# JETSON_AGX_UPHY.net
KiCad netlist of a schematic drawn in Altium Designer
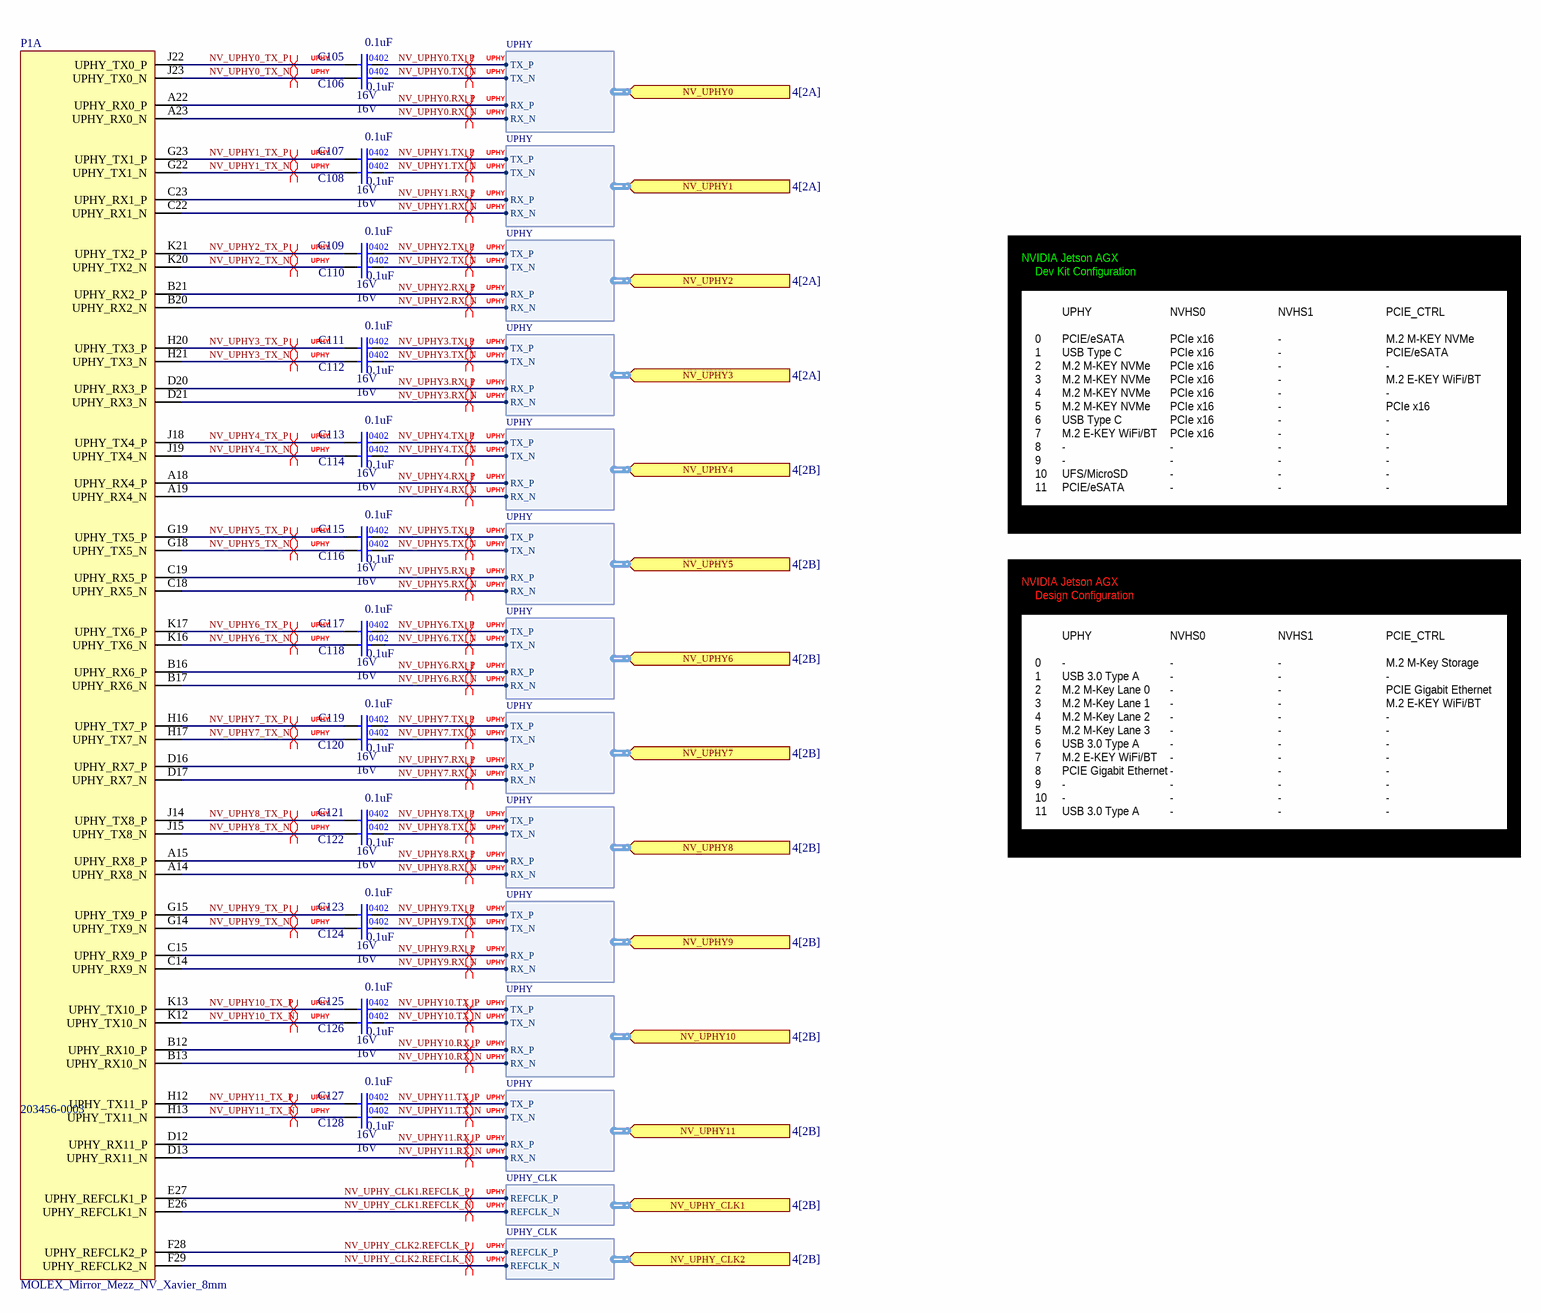
[diagram p0: JETSON AGX UPHY.SchDoc]

(export (version "E")
  (design (tool "Eeschema 10.0.6"))
  (components
    (comp (ref "C105")
      (value "CAP_0.1uF_16V_X7R_0402")
      (footprint "CAP0402")
      (description "CAP CER 0.1UF 16V X7R 0402")
      (fields (field (name "CAPACITANCE") "0.1uF") (field (name "VOLTAGE RATING") "16V"))
      (libsource (lib "UWRT_Schematic_Library_2020") (part "CAP_0.1uF_16V_X7R_0402"))
    )
    (comp (ref "C106")
      (value "CAP_0.1uF_16V_X7R_0402")
      (footprint "CAP0402")
      (description "CAP CER 0.1UF 16V X7R 0402")
      (fields (field (name "CAPACITANCE") "0.1uF") (field (name "VOLTAGE RATING") "16V"))
      (libsource (lib "UWRT_Schematic_Library_2020") (part "CAP_0.1uF_16V_X7R_0402"))
    )
    (comp (ref "C107")
      (value "CAP_0.1uF_16V_X7R_0402")
      (footprint "CAP0402")
      (description "CAP CER 0.1UF 16V X7R 0402")
      (fields (field (name "CAPACITANCE") "0.1uF") (field (name "VOLTAGE RATING") "16V"))
      (libsource (lib "UWRT_Schematic_Library_2020") (part "CAP_0.1uF_16V_X7R_0402"))
    )
    (comp (ref "C108")
      (value "CAP_0.1uF_16V_X7R_0402")
      (footprint "CAP0402")
      (description "CAP CER 0.1UF 16V X7R 0402")
      (fields (field (name "CAPACITANCE") "0.1uF") (field (name "VOLTAGE RATING") "16V"))
      (libsource (lib "UWRT_Schematic_Library_2020") (part "CAP_0.1uF_16V_X7R_0402"))
    )
    (comp (ref "C109")
      (value "CAP_0.1uF_16V_X7R_0402")
      (footprint "CAP0402")
      (description "CAP CER 0.1UF 16V X7R 0402")
      (fields (field (name "CAPACITANCE") "0.1uF") (field (name "VOLTAGE RATING") "16V"))
      (libsource (lib "UWRT_Schematic_Library_2020") (part "CAP_0.1uF_16V_X7R_0402"))
    )
    (comp (ref "C110")
      (value "CAP_0.1uF_16V_X7R_0402")
      (footprint "CAP0402")
      (description "CAP CER 0.1UF 16V X7R 0402")
      (fields (field (name "CAPACITANCE") "0.1uF") (field (name "VOLTAGE RATING") "16V"))
      (libsource (lib "UWRT_Schematic_Library_2020") (part "CAP_0.1uF_16V_X7R_0402"))
    )
    (comp (ref "C111")
      (value "CAP_0.1uF_16V_X7R_0402")
      (footprint "CAP0402")
      (description "CAP CER 0.1UF 16V X7R 0402")
      (fields (field (name "CAPACITANCE") "0.1uF") (field (name "VOLTAGE RATING") "16V"))
      (libsource (lib "UWRT_Schematic_Library_2020") (part "CAP_0.1uF_16V_X7R_0402"))
    )
    (comp (ref "C112")
      (value "CAP_0.1uF_16V_X7R_0402")
      (footprint "CAP0402")
      (description "CAP CER 0.1UF 16V X7R 0402")
      (fields (field (name "CAPACITANCE") "0.1uF") (field (name "VOLTAGE RATING") "16V"))
      (libsource (lib "UWRT_Schematic_Library_2020") (part "CAP_0.1uF_16V_X7R_0402"))
    )
    (comp (ref "C113")
      (value "CAP_0.1uF_16V_X7R_0402")
      (footprint "CAP0402")
      (description "CAP CER 0.1UF 16V X7R 0402")
      (fields (field (name "CAPACITANCE") "0.1uF") (field (name "VOLTAGE RATING") "16V"))
      (libsource (lib "UWRT_Schematic_Library_2020") (part "CAP_0.1uF_16V_X7R_0402"))
    )
    (comp (ref "C114")
      (value "CAP_0.1uF_16V_X7R_0402")
      (footprint "CAP0402")
      (description "CAP CER 0.1UF 16V X7R 0402")
      (fields (field (name "CAPACITANCE") "0.1uF") (field (name "VOLTAGE RATING") "16V"))
      (libsource (lib "UWRT_Schematic_Library_2020") (part "CAP_0.1uF_16V_X7R_0402"))
    )
    (comp (ref "C115")
      (value "CAP_0.1uF_16V_X7R_0402")
      (footprint "CAP0402")
      (description "CAP CER 0.1UF 16V X7R 0402")
      (fields (field (name "CAPACITANCE") "0.1uF") (field (name "VOLTAGE RATING") "16V"))
      (libsource (lib "UWRT_Schematic_Library_2020") (part "CAP_0.1uF_16V_X7R_0402"))
    )
    (comp (ref "C116")
      (value "CAP_0.1uF_16V_X7R_0402")
      (footprint "CAP0402")
      (description "CAP CER 0.1UF 16V X7R 0402")
      (fields (field (name "CAPACITANCE") "0.1uF") (field (name "VOLTAGE RATING") "16V"))
      (libsource (lib "UWRT_Schematic_Library_2020") (part "CAP_0.1uF_16V_X7R_0402"))
    )
    (comp (ref "C117")
      (value "CAP_0.1uF_16V_X7R_0402")
      (footprint "CAP0402")
      (description "CAP CER 0.1UF 16V X7R 0402")
      (fields (field (name "CAPACITANCE") "0.1uF") (field (name "VOLTAGE RATING") "16V"))
      (libsource (lib "UWRT_Schematic_Library_2020") (part "CAP_0.1uF_16V_X7R_0402"))
    )
    (comp (ref "C118")
      (value "CAP_0.1uF_16V_X7R_0402")
      (footprint "CAP0402")
      (description "CAP CER 0.1UF 16V X7R 0402")
      (fields (field (name "CAPACITANCE") "0.1uF") (field (name "VOLTAGE RATING") "16V"))
      (libsource (lib "UWRT_Schematic_Library_2020") (part "CAP_0.1uF_16V_X7R_0402"))
    )
    (comp (ref "C119")
      (value "CAP_0.1uF_16V_X7R_0402")
      (footprint "CAP0402")
      (description "CAP CER 0.1UF 16V X7R 0402")
      (fields (field (name "CAPACITANCE") "0.1uF") (field (name "VOLTAGE RATING") "16V"))
      (libsource (lib "UWRT_Schematic_Library_2020") (part "CAP_0.1uF_16V_X7R_0402"))
    )
    (comp (ref "C120")
      (value "CAP_0.1uF_16V_X7R_0402")
      (footprint "CAP0402")
      (description "CAP CER 0.1UF 16V X7R 0402")
      (fields (field (name "CAPACITANCE") "0.1uF") (field (name "VOLTAGE RATING") "16V"))
      (libsource (lib "UWRT_Schematic_Library_2020") (part "CAP_0.1uF_16V_X7R_0402"))
    )
    (comp (ref "C121")
      (value "CAP_0.1uF_16V_X7R_0402")
      (footprint "CAP0402")
      (description "CAP CER 0.1UF 16V X7R 0402")
      (fields (field (name "CAPACITANCE") "0.1uF") (field (name "VOLTAGE RATING") "16V"))
      (libsource (lib "UWRT_Schematic_Library_2020") (part "CAP_0.1uF_16V_X7R_0402"))
    )
    (comp (ref "C122")
      (value "CAP_0.1uF_16V_X7R_0402")
      (footprint "CAP0402")
      (description "CAP CER 0.1UF 16V X7R 0402")
      (fields (field (name "CAPACITANCE") "0.1uF") (field (name "VOLTAGE RATING") "16V"))
      (libsource (lib "UWRT_Schematic_Library_2020") (part "CAP_0.1uF_16V_X7R_0402"))
    )
    (comp (ref "C123")
      (value "CAP_0.1uF_16V_X7R_0402")
      (footprint "CAP0402")
      (description "CAP CER 0.1UF 16V X7R 0402")
      (fields (field (name "CAPACITANCE") "0.1uF") (field (name "VOLTAGE RATING") "16V"))
      (libsource (lib "UWRT_Schematic_Library_2020") (part "CAP_0.1uF_16V_X7R_0402"))
    )
    (comp (ref "C124")
      (value "CAP_0.1uF_16V_X7R_0402")
      (footprint "CAP0402")
      (description "CAP CER 0.1UF 16V X7R 0402")
      (fields (field (name "CAPACITANCE") "0.1uF") (field (name "VOLTAGE RATING") "16V"))
      (libsource (lib "UWRT_Schematic_Library_2020") (part "CAP_0.1uF_16V_X7R_0402"))
    )
    (comp (ref "C125")
      (value "CAP_0.1uF_16V_X7R_0402")
      (footprint "CAP0402")
      (description "CAP CER 0.1UF 16V X7R 0402")
      (fields (field (name "CAPACITANCE") "0.1uF") (field (name "VOLTAGE RATING") "16V"))
      (libsource (lib "UWRT_Schematic_Library_2020") (part "CAP_0.1uF_16V_X7R_0402"))
    )
    (comp (ref "C126")
      (value "CAP_0.1uF_16V_X7R_0402")
      (footprint "CAP0402")
      (description "CAP CER 0.1UF 16V X7R 0402")
      (fields (field (name "CAPACITANCE") "0.1uF") (field (name "VOLTAGE RATING") "16V"))
      (libsource (lib "UWRT_Schematic_Library_2020") (part "CAP_0.1uF_16V_X7R_0402"))
    )
    (comp (ref "C127")
      (value "CAP_0.1uF_16V_X7R_0402")
      (footprint "CAP0402")
      (description "CAP CER 0.1UF 16V X7R 0402")
      (fields (field (name "CAPACITANCE") "0.1uF") (field (name "VOLTAGE RATING") "16V"))
      (libsource (lib "UWRT_Schematic_Library_2020") (part "CAP_0.1uF_16V_X7R_0402"))
    )
    (comp (ref "C128")
      (value "CAP_0.1uF_16V_X7R_0402")
      (footprint "CAP0402")
      (description "CAP CER 0.1UF 16V X7R 0402")
      (fields (field (name "CAPACITANCE") "0.1uF") (field (name "VOLTAGE RATING") "16V"))
      (libsource (lib "UWRT_Schematic_Library_2020") (part "CAP_0.1uF_16V_X7R_0402"))
    )
    (comp (ref "P1")
      (value "MOLEX_Mirror_Mezz_NV_Xavier_8mm")
      (footprint "203456-0003")
      (description "CONN SELF-MATE 699POS SMD GOLD")
      (fields (field (name "MANUFACTURER PART NUMBER 1") "203456-0003"))
      (libsource (lib "UWRT_Schematic_Library_2020") (part "MOLEX_Mirror_Mezz_NV_Xavier_8mm"))
    )
  )
  (nets
    (net (code "3") (name "/NV_UPHY0.RX_N") (class "Default")
      (node (ref "P1") (pin "A23") (pinfunction "UPHY_RX0_N_A23") (pintype "passive"))
    )
    (net (code "4") (name "/NV_UPHY0.RX_P") (class "Default")
      (node (ref "P1") (pin "A22") (pinfunction "UPHY_RX0_P_A22") (pintype "passive"))
    )
    (net (code "5") (name "/NV_UPHY0.TX_N") (class "Default")
      (node (ref "C106") (pin "2") (pinfunction "2_2") (pintype "passive"))
    )
    (net (code "6") (name "/NV_UPHY0.TX_P") (class "Default")
      (node (ref "C105") (pin "2") (pinfunction "2_2") (pintype "passive"))
    )
    (net (code "7") (name "/NV_UPHY0_TX_N") (class "Default")
      (node (ref "C106") (pin "1") (pinfunction "1_1") (pintype "passive"))
      (node (ref "P1") (pin "J23") (pinfunction "UPHY_TX0_N_J23") (pintype "passive"))
    )
    (net (code "8") (name "/NV_UPHY0_TX_P") (class "Default")
      (node (ref "C105") (pin "1") (pinfunction "1_1") (pintype "passive"))
      (node (ref "P1") (pin "J22") (pinfunction "UPHY_TX0_P_J22") (pintype "passive"))
    )
    (net (code "9") (name "/NV_UPHY1.RX_N") (class "Default")
      (node (ref "P1") (pin "C22") (pinfunction "UPHY_RX1_N_C22") (pintype "passive"))
    )
    (net (code "10") (name "/NV_UPHY1.RX_P") (class "Default")
      (node (ref "P1") (pin "C23") (pinfunction "UPHY_RX1_P_C23") (pintype "passive"))
    )
    (net (code "11") (name "/NV_UPHY1.TX_N") (class "Default")
      (node (ref "C108") (pin "2") (pinfunction "2_2") (pintype "passive"))
    )
    (net (code "12") (name "/NV_UPHY1.TX_P") (class "Default")
      (node (ref "C107") (pin "2") (pinfunction "2_2") (pintype "passive"))
    )
    (net (code "13") (name "/NV_UPHY1_TX_N") (class "Default")
      (node (ref "C108") (pin "1") (pinfunction "1_1") (pintype "passive"))
      (node (ref "P1") (pin "G22") (pinfunction "UPHY_TX1_N_G22") (pintype "passive"))
    )
    (net (code "14") (name "/NV_UPHY1_TX_P") (class "Default")
      (node (ref "C107") (pin "1") (pinfunction "1_1") (pintype "passive"))
      (node (ref "P1") (pin "G23") (pinfunction "UPHY_TX1_P_G23") (pintype "passive"))
    )
    (net (code "15") (name "/NV_UPHY2.RX_N") (class "Default")
      (node (ref "P1") (pin "B20") (pinfunction "UPHY_RX2_N_B20") (pintype "passive"))
    )
    (net (code "16") (name "/NV_UPHY2.RX_P") (class "Default")
      (node (ref "P1") (pin "B21") (pinfunction "UPHY_RX2_P_B21") (pintype "passive"))
    )
    (net (code "17") (name "/NV_UPHY2.TX_N") (class "Default")
      (node (ref "C110") (pin "2") (pinfunction "2_2") (pintype "passive"))
    )
    (net (code "18") (name "/NV_UPHY2.TX_P") (class "Default")
      (node (ref "C109") (pin "2") (pinfunction "2_2") (pintype "passive"))
    )
    (net (code "19") (name "/NV_UPHY2_TX_N") (class "Default")
      (node (ref "C110") (pin "1") (pinfunction "1_1") (pintype "passive"))
      (node (ref "P1") (pin "K20") (pinfunction "UPHY_TX2_N_K20") (pintype "passive"))
    )
    (net (code "20") (name "/NV_UPHY2_TX_P") (class "Default")
      (node (ref "C109") (pin "1") (pinfunction "1_1") (pintype "passive"))
      (node (ref "P1") (pin "K21") (pinfunction "UPHY_TX2_P_K21") (pintype "passive"))
    )
    (net (code "21") (name "/NV_UPHY3.RX_N") (class "Default")
      (node (ref "P1") (pin "D21") (pinfunction "UPHY_RX3_N_D21") (pintype "passive"))
    )
    (net (code "22") (name "/NV_UPHY3.RX_P") (class "Default")
      (node (ref "P1") (pin "D20") (pinfunction "UPHY_RX3_P_D20") (pintype "passive"))
    )
    (net (code "23") (name "/NV_UPHY3.TX_N") (class "Default")
      (node (ref "C112") (pin "2") (pinfunction "2_2") (pintype "passive"))
    )
    (net (code "24") (name "/NV_UPHY3.TX_P") (class "Default")
      (node (ref "C111") (pin "2") (pinfunction "2_2") (pintype "passive"))
    )
    (net (code "25") (name "/NV_UPHY3_TX_N") (class "Default")
      (node (ref "C112") (pin "1") (pinfunction "1_1") (pintype "passive"))
      (node (ref "P1") (pin "H21") (pinfunction "UPHY_TX3_N_H21") (pintype "passive"))
    )
    (net (code "26") (name "/NV_UPHY3_TX_P") (class "Default")
      (node (ref "C111") (pin "1") (pinfunction "1_1") (pintype "passive"))
      (node (ref "P1") (pin "H20") (pinfunction "UPHY_TX3_P_H20") (pintype "passive"))
    )
    (net (code "27") (name "/NV_UPHY4.RX_N") (class "Default")
      (node (ref "P1") (pin "A19") (pinfunction "UPHY_RX4_N_A19") (pintype "passive"))
    )
    (net (code "28") (name "/NV_UPHY4.RX_P") (class "Default")
      (node (ref "P1") (pin "A18") (pinfunction "UPHY_RX4_P_A18") (pintype "passive"))
    )
    (net (code "29") (name "/NV_UPHY4.TX_N") (class "Default")
      (node (ref "C114") (pin "2") (pinfunction "2_2") (pintype "passive"))
    )
    (net (code "30") (name "/NV_UPHY4.TX_P") (class "Default")
      (node (ref "C113") (pin "2") (pinfunction "2_2") (pintype "passive"))
    )
    (net (code "31") (name "/NV_UPHY4_TX_N") (class "Default")
      (node (ref "C114") (pin "1") (pinfunction "1_1") (pintype "passive"))
      (node (ref "P1") (pin "J19") (pinfunction "UPHY_TX4_N_J19") (pintype "passive"))
    )
    (net (code "32") (name "/NV_UPHY4_TX_P") (class "Default")
      (node (ref "C113") (pin "1") (pinfunction "1_1") (pintype "passive"))
      (node (ref "P1") (pin "J18") (pinfunction "UPHY_TX4_P_J18") (pintype "passive"))
    )
    (net (code "33") (name "/NV_UPHY5.RX_N") (class "Default")
      (node (ref "P1") (pin "C18") (pinfunction "UPHY_RX5_N_C18") (pintype "passive"))
    )
    (net (code "34") (name "/NV_UPHY5.RX_P") (class "Default")
      (node (ref "P1") (pin "C19") (pinfunction "UPHY_RX5_P_C19") (pintype "passive"))
    )
    (net (code "35") (name "/NV_UPHY5.TX_N") (class "Default")
      (node (ref "C116") (pin "2") (pinfunction "2_2") (pintype "passive"))
    )
    (net (code "36") (name "/NV_UPHY5.TX_P") (class "Default")
      (node (ref "C115") (pin "2") (pinfunction "2_2") (pintype "passive"))
    )
    (net (code "37") (name "/NV_UPHY5_TX_N") (class "Default")
      (node (ref "C116") (pin "1") (pinfunction "1_1") (pintype "passive"))
      (node (ref "P1") (pin "G18") (pinfunction "UPHY_TX5_N_G18") (pintype "passive"))
    )
    (net (code "38") (name "/NV_UPHY5_TX_P") (class "Default")
      (node (ref "C115") (pin "1") (pinfunction "1_1") (pintype "passive"))
      (node (ref "P1") (pin "G19") (pinfunction "UPHY_TX5_P_G19") (pintype "passive"))
    )
    (net (code "39") (name "/NV_UPHY6.RX_N") (class "Default")
      (node (ref "P1") (pin "B17") (pinfunction "UPHY_RX6_N_B17") (pintype "passive"))
    )
    (net (code "40") (name "/NV_UPHY6.RX_P") (class "Default")
      (node (ref "P1") (pin "B16") (pinfunction "UPHY_RX6_P_B16") (pintype "passive"))
    )
    (net (code "41") (name "/NV_UPHY6.TX_N") (class "Default")
      (node (ref "C118") (pin "2") (pinfunction "2_2") (pintype "passive"))
    )
    (net (code "42") (name "/NV_UPHY6.TX_P") (class "Default")
      (node (ref "C117") (pin "2") (pinfunction "2_2") (pintype "passive"))
    )
    (net (code "43") (name "/NV_UPHY6_TX_N") (class "Default")
      (node (ref "C118") (pin "1") (pinfunction "1_1") (pintype "passive"))
      (node (ref "P1") (pin "K16") (pinfunction "UPHY_TX6_N_K16") (pintype "passive"))
    )
    (net (code "44") (name "/NV_UPHY6_TX_P") (class "Default")
      (node (ref "C117") (pin "1") (pinfunction "1_1") (pintype "passive"))
      (node (ref "P1") (pin "K17") (pinfunction "UPHY_TX6_P_K17") (pintype "passive"))
    )
    (net (code "45") (name "/NV_UPHY7.RX_N") (class "Default")
      (node (ref "P1") (pin "D17") (pinfunction "UPHY_RX7_N_D17") (pintype "passive"))
    )
    (net (code "46") (name "/NV_UPHY7.RX_P") (class "Default")
      (node (ref "P1") (pin "D16") (pinfunction "UPHY_RX7_P_D16") (pintype "passive"))
    )
    (net (code "47") (name "/NV_UPHY7.TX_N") (class "Default")
      (node (ref "C120") (pin "2") (pinfunction "2_2") (pintype "passive"))
    )
    (net (code "48") (name "/NV_UPHY7.TX_P") (class "Default")
      (node (ref "C119") (pin "2") (pinfunction "2_2") (pintype "passive"))
    )
    (net (code "49") (name "/NV_UPHY7_TX_N") (class "Default")
      (node (ref "C120") (pin "1") (pinfunction "1_1") (pintype "passive"))
      (node (ref "P1") (pin "H17") (pinfunction "UPHY_TX7_N_H17") (pintype "passive"))
    )
    (net (code "50") (name "/NV_UPHY7_TX_P") (class "Default")
      (node (ref "C119") (pin "1") (pinfunction "1_1") (pintype "passive"))
      (node (ref "P1") (pin "H16") (pinfunction "UPHY_TX7_P_H16") (pintype "passive"))
    )
    (net (code "51") (name "/NV_UPHY8.RX_N") (class "Default")
      (node (ref "P1") (pin "A14") (pinfunction "UPHY_RX8_N_A14") (pintype "passive"))
    )
    (net (code "52") (name "/NV_UPHY8.RX_P") (class "Default")
      (node (ref "P1") (pin "A15") (pinfunction "UPHY_RX8_P_A15") (pintype "passive"))
    )
    (net (code "53") (name "/NV_UPHY8.TX_N") (class "Default")
      (node (ref "C122") (pin "2") (pinfunction "2_2") (pintype "passive"))
    )
    (net (code "54") (name "/NV_UPHY8.TX_P") (class "Default")
      (node (ref "C121") (pin "2") (pinfunction "2_2") (pintype "passive"))
    )
    (net (code "55") (name "/NV_UPHY8_TX_N") (class "Default")
      (node (ref "C122") (pin "1") (pinfunction "1_1") (pintype "passive"))
      (node (ref "P1") (pin "J15") (pinfunction "UPHY_TX8_N_J15") (pintype "passive"))
    )
    (net (code "56") (name "/NV_UPHY8_TX_P") (class "Default")
      (node (ref "C121") (pin "1") (pinfunction "1_1") (pintype "passive"))
      (node (ref "P1") (pin "J14") (pinfunction "UPHY_TX8_P_J14") (pintype "passive"))
    )
    (net (code "57") (name "/NV_UPHY9.RX_N") (class "Default")
      (node (ref "P1") (pin "C14") (pinfunction "UPHY_RX9_N_C14") (pintype "passive"))
    )
    (net (code "58") (name "/NV_UPHY9.RX_P") (class "Default")
      (node (ref "P1") (pin "C15") (pinfunction "UPHY_RX9_P_C15") (pintype "passive"))
    )
    (net (code "59") (name "/NV_UPHY9.TX_N") (class "Default")
      (node (ref "C124") (pin "2") (pinfunction "2_2") (pintype "passive"))
    )
    (net (code "60") (name "/NV_UPHY9.TX_P") (class "Default")
      (node (ref "C123") (pin "2") (pinfunction "2_2") (pintype "passive"))
    )
    (net (code "61") (name "/NV_UPHY9_TX_N") (class "Default")
      (node (ref "C124") (pin "1") (pinfunction "1_1") (pintype "passive"))
      (node (ref "P1") (pin "G14") (pinfunction "UPHY_TX9_N_G14") (pintype "passive"))
    )
    (net (code "62") (name "/NV_UPHY9_TX_P") (class "Default")
      (node (ref "C123") (pin "1") (pinfunction "1_1") (pintype "passive"))
      (node (ref "P1") (pin "G15") (pinfunction "UPHY_TX9_P_G15") (pintype "passive"))
    )
    (net (code "63") (name "/NV_UPHY10.RX_N") (class "Default")
      (node (ref "P1") (pin "B13") (pinfunction "UPHY_RX10_N_B13") (pintype "passive"))
    )
    (net (code "64") (name "/NV_UPHY10.RX_P") (class "Default")
      (node (ref "P1") (pin "B12") (pinfunction "UPHY_RX10_P_B12") (pintype "passive"))
    )
    (net (code "65") (name "/NV_UPHY10.TX_N") (class "Default")
      (node (ref "C126") (pin "2") (pinfunction "2_2") (pintype "passive"))
    )
    (net (code "66") (name "/NV_UPHY10.TX_P") (class "Default")
      (node (ref "C125") (pin "2") (pinfunction "2_2") (pintype "passive"))
    )
    (net (code "67") (name "/NV_UPHY10_TX_N") (class "Default")
      (node (ref "C126") (pin "1") (pinfunction "1_1") (pintype "passive"))
      (node (ref "P1") (pin "K12") (pinfunction "UPHY_TX10_N_K12") (pintype "passive"))
    )
    (net (code "68") (name "/NV_UPHY10_TX_P") (class "Default")
      (node (ref "C125") (pin "1") (pinfunction "1_1") (pintype "passive"))
      (node (ref "P1") (pin "K13") (pinfunction "UPHY_TX10_P_K13") (pintype "passive"))
    )
    (net (code "69") (name "/NV_UPHY11.RX_N") (class "Default")
      (node (ref "P1") (pin "D13") (pinfunction "UPHY_RX11_N_D13") (pintype "passive"))
    )
    (net (code "70") (name "/NV_UPHY11.RX_P") (class "Default")
      (node (ref "P1") (pin "D12") (pinfunction "UPHY_RX11_P_D12") (pintype "passive"))
    )
    (net (code "71") (name "/NV_UPHY11.TX_N") (class "Default")
      (node (ref "C128") (pin "2") (pinfunction "2_2") (pintype "passive"))
    )
    (net (code "72") (name "/NV_UPHY11.TX_P") (class "Default")
      (node (ref "C127") (pin "2") (pinfunction "2_2") (pintype "passive"))
    )
    (net (code "73") (name "/NV_UPHY11_TX_N") (class "Default")
      (node (ref "C128") (pin "1") (pinfunction "1_1") (pintype "passive"))
      (node (ref "P1") (pin "H13") (pinfunction "UPHY_TX11_N_H13") (pintype "passive"))
    )
    (net (code "74") (name "/NV_UPHY11_TX_P") (class "Default")
      (node (ref "C127") (pin "1") (pinfunction "1_1") (pintype "passive"))
      (node (ref "P1") (pin "H12") (pinfunction "UPHY_TX11_P_H12") (pintype "passive"))
    )
    (net (code "75") (name "/NV_UPHY_CLK1.REFCLK_N") (class "Default")
      (node (ref "P1") (pin "E26") (pinfunction "UPHY_REFCLK1_N_E26") (pintype "passive"))
    )
    (net (code "76") (name "/NV_UPHY_CLK1.REFCLK_P") (class "Default")
      (node (ref "P1") (pin "E27") (pinfunction "UPHY_REFCLK1_P_E27") (pintype "passive"))
    )
    (net (code "77") (name "/NV_UPHY_CLK2.REFCLK_N") (class "Default")
      (node (ref "P1") (pin "F29") (pinfunction "UPHY_REFCLK2_N_F29") (pintype "passive"))
    )
    (net (code "78") (name "/NV_UPHY_CLK2.REFCLK_P") (class "Default")
      (node (ref "P1") (pin "F28") (pinfunction "UPHY_REFCLK2_P_F28") (pintype "passive"))
    )
  )
)
